# DS2408_8S.net
KiCad netlist of a schematic drawn in EAGLE
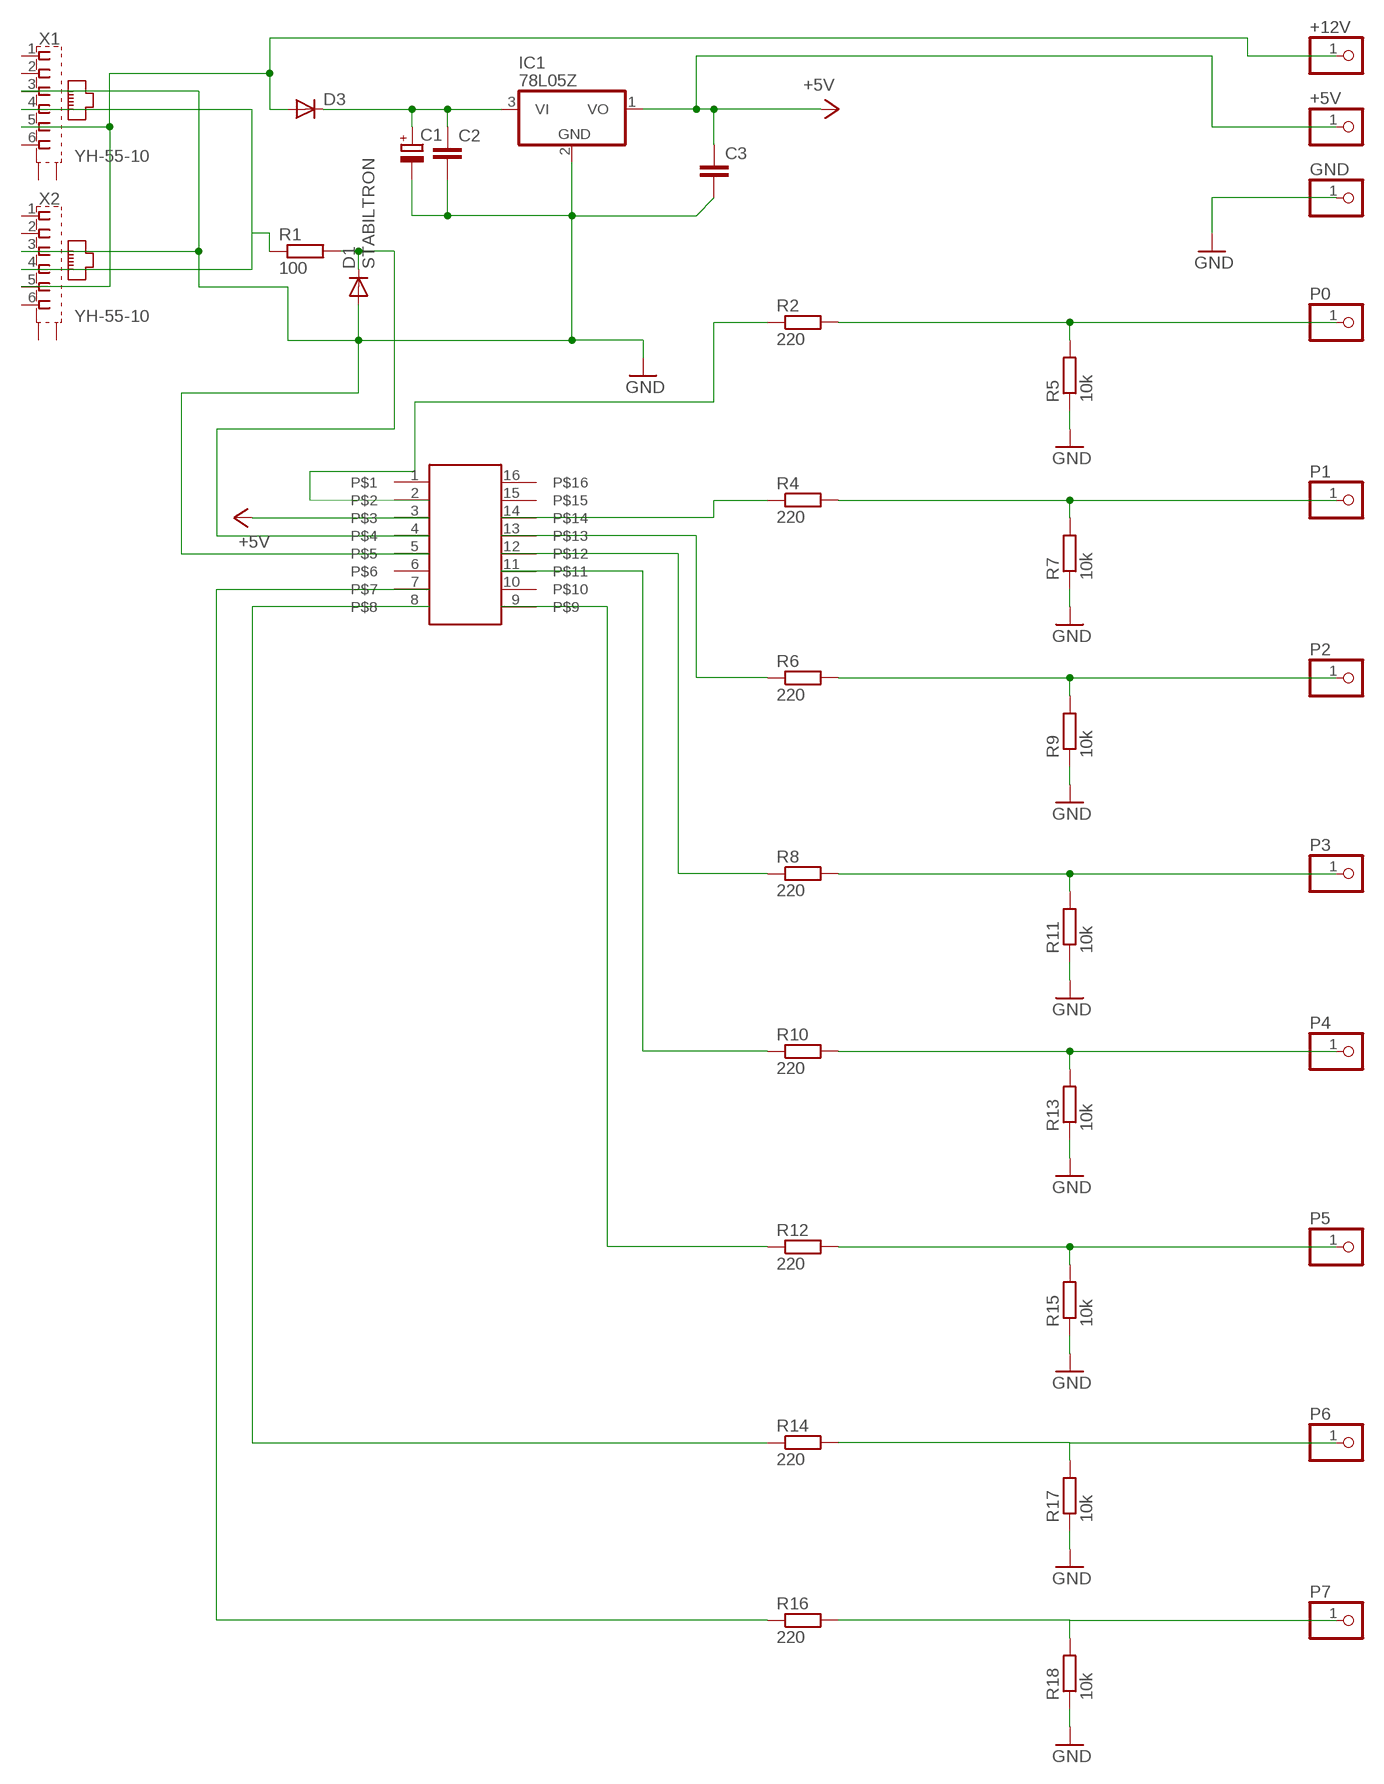
[diagram p0: schematic, sheet 1]

(export (version "E")
  (design (tool "Eeschema 10.0.6"))
  (components
    (comp (ref "+5V")
      (value "PINHD-1X1")
      (footprint "eagle-import:1X01")
      (libsource (lib "eagle-import") (part "PINHD-1X1"))
    )
    (comp (ref "+12V")
      (value "PINHD-1X1")
      (footprint "eagle-import:1X01")
      (libsource (lib "eagle-import") (part "PINHD-1X1"))
    )
    (comp (ref "C1")
      (value "CPOL-EUE5-10.5")
      (footprint "eagle-import:E5-10,5")
      (libsource (lib "eagle-import") (part "CPOL-EUE5-10.5"))
    )
    (comp (ref "C2")
      (value "C-EUC1206")
      (footprint "eagle-import:C1206")
      (libsource (lib "eagle-import") (part "C-EUC1206"))
    )
    (comp (ref "C3")
      (value "C-EUC1206")
      (footprint "eagle-import:C1206")
      (libsource (lib "eagle-import") (part "C-EUC1206"))
    )
    (comp (ref "D1")
      (value "STABILTRON")
      (footprint "eagle-import:DO35-10")
      (libsource (lib "eagle-import") (part "1N4148DO35-10"))
    )
    (comp (ref "D3")
      (value "DIODE-MINIMELF")
      (footprint "eagle-import:MINIMELF")
      (libsource (lib "eagle-import") (part "DIODE-MINIMELF"))
    )
    (comp (ref "GND")
      (value "PINHD-1X1")
      (footprint "eagle-import:1X01")
      (libsource (lib "eagle-import") (part "PINHD-1X1"))
    )
    (comp (ref "IC1")
      (value "78L05Z")
      (footprint "eagle-import:TO92")
      (libsource (lib "eagle-import") (part "78ZL05"))
    )
    (comp (ref "P0")
      (value "PINHD-1X1")
      (footprint "eagle-import:1X01")
      (libsource (lib "eagle-import") (part "PINHD-1X1"))
    )
    (comp (ref "P1")
      (value "PINHD-1X1")
      (footprint "eagle-import:1X01")
      (libsource (lib "eagle-import") (part "PINHD-1X1"))
    )
    (comp (ref "P2")
      (value "PINHD-1X1")
      (footprint "eagle-import:1X01")
      (libsource (lib "eagle-import") (part "PINHD-1X1"))
    )
    (comp (ref "P3")
      (value "PINHD-1X1")
      (footprint "eagle-import:1X01")
      (libsource (lib "eagle-import") (part "PINHD-1X1"))
    )
    (comp (ref "P4")
      (value "PINHD-1X1")
      (footprint "eagle-import:1X01")
      (libsource (lib "eagle-import") (part "PINHD-1X1"))
    )
    (comp (ref "P5")
      (value "PINHD-1X1")
      (footprint "eagle-import:1X01")
      (libsource (lib "eagle-import") (part "PINHD-1X1"))
    )
    (comp (ref "P6")
      (value "PINHD-1X1")
      (footprint "eagle-import:1X01")
      (libsource (lib "eagle-import") (part "PINHD-1X1"))
    )
    (comp (ref "P7")
      (value "PINHD-1X1")
      (footprint "eagle-import:1X01")
      (libsource (lib "eagle-import") (part "PINHD-1X1"))
    )
    (comp (ref "R1")
      (value "100")
      (footprint "eagle-import:M1206")
      (libsource (lib "eagle-import") (part "R-EU_M1206"))
    )
    (comp (ref "R2")
      (value "220")
      (footprint "eagle-import:M1206")
      (libsource (lib "eagle-import") (part "R-EU_M1206"))
    )
    (comp (ref "R4")
      (value "220")
      (footprint "eagle-import:M1206")
      (libsource (lib "eagle-import") (part "R-EU_M1206"))
    )
    (comp (ref "R5")
      (value "10k")
      (footprint "eagle-import:M1206")
      (libsource (lib "eagle-import") (part "R-EU_M1206"))
    )
    (comp (ref "R6")
      (value "220")
      (footprint "eagle-import:M1206")
      (libsource (lib "eagle-import") (part "R-EU_M1206"))
    )
    (comp (ref "R7")
      (value "10k")
      (footprint "eagle-import:M1206")
      (libsource (lib "eagle-import") (part "R-EU_M1206"))
    )
    (comp (ref "R8")
      (value "220")
      (footprint "eagle-import:M1206")
      (libsource (lib "eagle-import") (part "R-EU_M1206"))
    )
    (comp (ref "R9")
      (value "10k")
      (footprint "eagle-import:M1206")
      (libsource (lib "eagle-import") (part "R-EU_M1206"))
    )
    (comp (ref "R10")
      (value "220")
      (footprint "eagle-import:M1206")
      (libsource (lib "eagle-import") (part "R-EU_M1206"))
    )
    (comp (ref "R11")
      (value "10k")
      (footprint "eagle-import:M1206")
      (libsource (lib "eagle-import") (part "R-EU_M1206"))
    )
    (comp (ref "R12")
      (value "220")
      (footprint "eagle-import:M1206")
      (libsource (lib "eagle-import") (part "R-EU_M1206"))
    )
    (comp (ref "R13")
      (value "10k")
      (footprint "eagle-import:M1206")
      (libsource (lib "eagle-import") (part "R-EU_M1206"))
    )
    (comp (ref "R14")
      (value "220")
      (footprint "eagle-import:M1206")
      (libsource (lib "eagle-import") (part "R-EU_M1206"))
    )
    (comp (ref "R15")
      (value "10k")
      (footprint "eagle-import:M1206")
      (libsource (lib "eagle-import") (part "R-EU_M1206"))
    )
    (comp (ref "R16")
      (value "220")
      (footprint "eagle-import:M1206")
      (libsource (lib "eagle-import") (part "R-EU_M1206"))
    )
    (comp (ref "R17")
      (value "10k")
      (footprint "eagle-import:M1206")
      (libsource (lib "eagle-import") (part "R-EU_M1206"))
    )
    (comp (ref "R18")
      (value "10k")
      (footprint "eagle-import:M1206")
      (libsource (lib "eagle-import") (part "R-EU_M1206"))
    )
    (comp (ref "U$1")
      (value "DS2408S")
      (footprint "eagle-import:SO16")
      (libsource (lib "eagle-import") (part "DS2408S"))
    )
    (comp (ref "X1")
      (value "YH-55-10")
      (footprint "eagle-import:YH-55-10")
      (libsource (lib "eagle-import") (part "YH-55-10"))
    )
    (comp (ref "X2")
      (value "YH-55-10")
      (footprint "eagle-import:YH-55-10")
      (libsource (lib "eagle-import") (part "YH-55-10"))
    )
  )
  (nets
    (net (code "1") (name "+5V") (class "Default")
      (node (ref "+5V") (pin "1") (pinfunction "1_1") (pintype "passive"))
      (node (ref "C3") (pin "1") (pinfunction "1_1") (pintype "passive"))
      (node (ref "IC1") (pin "1") (pinfunction "VO_1") (pintype "passive"))
      (node (ref "U$1") (pin "3") (pinfunction "P$3_3") (pintype "bidirectional"))
    )
    (net (code "2") (name "GND") (class "Default")
      (node (ref "C1") (pin "-") (pinfunction "-_-") (pintype "passive"))
      (node (ref "C2") (pin "2") (pinfunction "2_2") (pintype "passive"))
      (node (ref "C3") (pin "2") (pinfunction "2_2") (pintype "passive"))
      (node (ref "D1") (pin "A") (pinfunction "A_A") (pintype "passive"))
      (node (ref "GND") (pin "1") (pinfunction "1_1") (pintype "passive"))
      (node (ref "IC1") (pin "2") (pinfunction "GND_2") (pintype "passive"))
      (node (ref "R11") (pin "1") (pinfunction "1_1") (pintype "passive"))
      (node (ref "R13") (pin "1") (pinfunction "1_1") (pintype "passive"))
      (node (ref "R15") (pin "1") (pinfunction "1_1") (pintype "passive"))
      (node (ref "R17") (pin "1") (pinfunction "1_1") (pintype "passive"))
      (node (ref "R18") (pin "1") (pinfunction "1_1") (pintype "passive"))
      (node (ref "R5") (pin "1") (pinfunction "1_1") (pintype "passive"))
      (node (ref "R7") (pin "1") (pinfunction "1_1") (pintype "passive"))
      (node (ref "R9") (pin "1") (pinfunction "1_1") (pintype "passive"))
      (node (ref "U$1") (pin "5") (pinfunction "P$5_5") (pintype "bidirectional"))
      (node (ref "X1") (pin "3") (pinfunction "3_3") (pintype "passive"))
      (node (ref "X2") (pin "3") (pinfunction "3_3") (pintype "passive"))
    )
    (net (code "3") (name "Net-(+12V-Pad1)") (class "Default")
      (node (ref "+12V") (pin "1") (pinfunction "1_1") (pintype "passive"))
      (node (ref "D3") (pin "A") (pinfunction "A_A") (pintype "passive"))
      (node (ref "X1") (pin "5") (pinfunction "5_5") (pintype "passive"))
      (node (ref "X2") (pin "5") (pinfunction "5_5") (pintype "passive"))
    )
    (net (code "4") (name "Net-(IC1-VI)") (class "Default")
      (node (ref "C1") (pin "+") (pinfunction "+_+") (pintype "passive"))
      (node (ref "C2") (pin "1") (pinfunction "1_1") (pintype "passive"))
      (node (ref "D3") (pin "C") (pinfunction "C_C") (pintype "passive"))
      (node (ref "IC1") (pin "3") (pinfunction "VI_3") (pintype "input"))
    )
    (net (code "5") (name "Net-(P0-Pad1)") (class "Default")
      (node (ref "P0") (pin "1") (pinfunction "1_1") (pintype "passive"))
      (node (ref "R2") (pin "2") (pinfunction "2_2") (pintype "passive"))
      (node (ref "R5") (pin "2") (pinfunction "2_2") (pintype "passive"))
    )
    (net (code "6") (name "Net-(P1-Pad1)") (class "Default")
      (node (ref "P1") (pin "1") (pinfunction "1_1") (pintype "passive"))
      (node (ref "R4") (pin "2") (pinfunction "2_2") (pintype "passive"))
      (node (ref "R7") (pin "2") (pinfunction "2_2") (pintype "passive"))
    )
    (net (code "7") (name "Net-(P2-Pad1)") (class "Default")
      (node (ref "P2") (pin "1") (pinfunction "1_1") (pintype "passive"))
      (node (ref "R6") (pin "2") (pinfunction "2_2") (pintype "passive"))
      (node (ref "R9") (pin "2") (pinfunction "2_2") (pintype "passive"))
    )
    (net (code "8") (name "Net-(P3-Pad1)") (class "Default")
      (node (ref "P3") (pin "1") (pinfunction "1_1") (pintype "passive"))
      (node (ref "R11") (pin "2") (pinfunction "2_2") (pintype "passive"))
      (node (ref "R8") (pin "2") (pinfunction "2_2") (pintype "passive"))
    )
    (net (code "9") (name "Net-(P4-Pad1)") (class "Default")
      (node (ref "P4") (pin "1") (pinfunction "1_1") (pintype "passive"))
      (node (ref "R10") (pin "2") (pinfunction "2_2") (pintype "passive"))
      (node (ref "R13") (pin "2") (pinfunction "2_2") (pintype "passive"))
    )
    (net (code "10") (name "Net-(P5-Pad1)") (class "Default")
      (node (ref "P5") (pin "1") (pinfunction "1_1") (pintype "passive"))
      (node (ref "R12") (pin "2") (pinfunction "2_2") (pintype "passive"))
      (node (ref "R15") (pin "2") (pinfunction "2_2") (pintype "passive"))
    )
    (net (code "11") (name "Net-(P6-Pad1)") (class "Default")
      (node (ref "P6") (pin "1") (pinfunction "1_1") (pintype "passive"))
      (node (ref "R14") (pin "2") (pinfunction "2_2") (pintype "passive"))
      (node (ref "R17") (pin "2") (pinfunction "2_2") (pintype "passive"))
    )
    (net (code "12") (name "Net-(P7-Pad1)") (class "Default")
      (node (ref "P7") (pin "1") (pinfunction "1_1") (pintype "passive"))
      (node (ref "R16") (pin "2") (pinfunction "2_2") (pintype "passive"))
      (node (ref "R18") (pin "2") (pinfunction "2_2") (pintype "passive"))
    )
    (net (code "13") (name "Net-(R1-Pad1)") (class "Default")
      (node (ref "R1") (pin "1") (pinfunction "1_1") (pintype "passive"))
      (node (ref "X1") (pin "4") (pinfunction "4_4") (pintype "passive"))
      (node (ref "X2") (pin "4") (pinfunction "4_4") (pintype "passive"))
    )
    (net (code "14") (name "Net-(U$1-P$2)") (class "Default")
      (node (ref "R2") (pin "1") (pinfunction "1_1") (pintype "passive"))
      (node (ref "U$1") (pin "2") (pinfunction "P$2_2") (pintype "bidirectional"))
    )
    (net (code "15") (name "Net-(U$1-P$4)") (class "Default")
      (node (ref "D1") (pin "C") (pinfunction "C_C") (pintype "passive"))
      (node (ref "R1") (pin "2") (pinfunction "2_2") (pintype "passive"))
      (node (ref "U$1") (pin "4") (pinfunction "P$4_4") (pintype "bidirectional"))
    )
    (net (code "16") (name "Net-(U$1-P$7)") (class "Default")
      (node (ref "R16") (pin "1") (pinfunction "1_1") (pintype "passive"))
      (node (ref "U$1") (pin "7") (pinfunction "P$7_7") (pintype "bidirectional"))
    )
    (net (code "17") (name "Net-(U$1-P$8)") (class "Default")
      (node (ref "R14") (pin "1") (pinfunction "1_1") (pintype "passive"))
      (node (ref "U$1") (pin "8") (pinfunction "P$8_8") (pintype "bidirectional"))
    )
    (net (code "18") (name "Net-(U$1-P$9)") (class "Default")
      (node (ref "R12") (pin "1") (pinfunction "1_1") (pintype "passive"))
      (node (ref "U$1") (pin "9") (pinfunction "P$9_9") (pintype "bidirectional"))
    )
    (net (code "19") (name "Net-(U$1-P$11)") (class "Default")
      (node (ref "R10") (pin "1") (pinfunction "1_1") (pintype "passive"))
      (node (ref "U$1") (pin "11") (pinfunction "P$11_11") (pintype "bidirectional"))
    )
    (net (code "20") (name "Net-(U$1-P$12)") (class "Default")
      (node (ref "R8") (pin "1") (pinfunction "1_1") (pintype "passive"))
      (node (ref "U$1") (pin "12") (pinfunction "P$12_12") (pintype "bidirectional"))
    )
    (net (code "21") (name "Net-(U$1-P$13)") (class "Default")
      (node (ref "R6") (pin "1") (pinfunction "1_1") (pintype "passive"))
      (node (ref "U$1") (pin "13") (pinfunction "P$13_13") (pintype "bidirectional"))
    )
    (net (code "22") (name "Net-(U$1-P$14)") (class "Default")
      (node (ref "R4") (pin "1") (pinfunction "1_1") (pintype "passive"))
      (node (ref "U$1") (pin "14") (pinfunction "P$14_14") (pintype "bidirectional"))
    )
    (net (code "23") (name "unconnected-(U$1-P$1-Pad1)") (class "Default")
      (node (ref "U$1") (pin "1") (pinfunction "P$1_1") (pintype "bidirectional"))
    )
    (net (code "24") (name "unconnected-(U$1-P$6-Pad6)") (class "Default")
      (node (ref "U$1") (pin "6") (pinfunction "P$6_6") (pintype "bidirectional"))
    )
    (net (code "25") (name "unconnected-(U$1-P$10-Pad10)") (class "Default")
      (node (ref "U$1") (pin "10") (pinfunction "P$10_10") (pintype "bidirectional"))
    )
    (net (code "26") (name "unconnected-(U$1-P$15-Pad15)") (class "Default")
      (node (ref "U$1") (pin "15") (pinfunction "P$15_15") (pintype "bidirectional"))
    )
    (net (code "27") (name "unconnected-(U$1-P$16-Pad16)") (class "Default")
      (node (ref "U$1") (pin "16") (pinfunction "P$16_16") (pintype "bidirectional"))
    )
    (net (code "28") (name "unconnected-(X1-Pad1)") (class "Default")
      (node (ref "X1") (pin "1") (pinfunction "1_1") (pintype "passive"))
    )
    (net (code "29") (name "unconnected-(X1-Pad2)") (class "Default")
      (node (ref "X1") (pin "2") (pinfunction "2_2") (pintype "passive"))
    )
    (net (code "30") (name "unconnected-(X1-Pad6)") (class "Default")
      (node (ref "X1") (pin "6") (pinfunction "6_6") (pintype "passive"))
    )
    (net (code "31") (name "unconnected-(X1-S-PadS1)") (class "Default")
      (node (ref "X1") (pin "S1") (pinfunction "S_S1") (pintype "passive"))
    )
    (net (code "32") (name "unconnected-(X1-S-PadS2)") (class "Default")
      (node (ref "X1") (pin "S2") (pinfunction "S_S2") (pintype "passive"))
    )
    (net (code "33") (name "unconnected-(X2-Pad1)") (class "Default")
      (node (ref "X2") (pin "1") (pinfunction "1_1") (pintype "passive"))
    )
    (net (code "34") (name "unconnected-(X2-Pad2)") (class "Default")
      (node (ref "X2") (pin "2") (pinfunction "2_2") (pintype "passive"))
    )
    (net (code "35") (name "unconnected-(X2-Pad6)") (class "Default")
      (node (ref "X2") (pin "6") (pinfunction "6_6") (pintype "passive"))
    )
    (net (code "36") (name "unconnected-(X2-S-PadS1)") (class "Default")
      (node (ref "X2") (pin "S1") (pinfunction "S_S1") (pintype "passive"))
    )
    (net (code "37") (name "unconnected-(X2-S-PadS2)") (class "Default")
      (node (ref "X2") (pin "S2") (pinfunction "S_S2") (pintype "passive"))
    )
  )
)
